# Analog_Inputs.net
KiCad netlist of a schematic drawn in Altium Designer
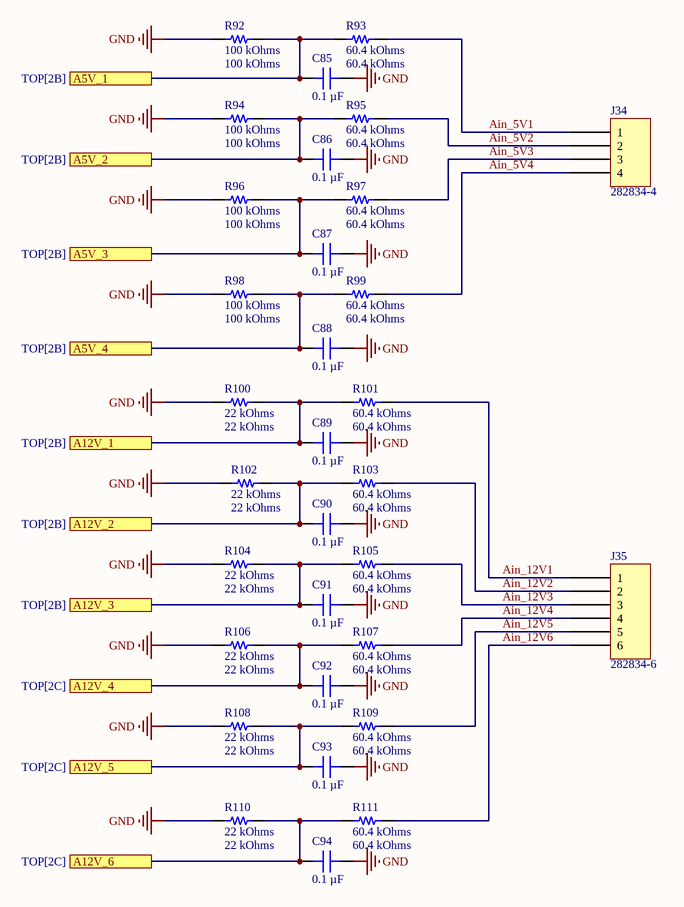
[diagram p0: Analog Inputs.SchDoc]

(export (version "E")
  (design (tool "Eeschema 10.0.6"))
  (components
    (comp (ref "C85")
      (value "0.1 µF")
      (footprint "CAP 0603_1608")
      (description "CAP CER 0.1UF 6.3V X7R 0603")
      (fields
        (field (name "PART NUMBER") "6R3X14W104MV4T")
        (field (name "MANUFACTURER") "Johanson Dielectrics Inc.")
      )
      (libsource (lib "altium_library") (part "Capacitor"))
    )
    (comp (ref "C86")
      (value "0.1 µF")
      (footprint "CAP 0603_1608")
      (description "CAP CER 0.1UF 6.3V X7R 0603")
      (fields
        (field (name "PART NUMBER") "6R3X14W104MV4T")
        (field (name "MANUFACTURER") "Johanson Dielectrics Inc.")
      )
      (libsource (lib "altium_library") (part "Capacitor"))
    )
    (comp (ref "C87")
      (value "0.1 µF")
      (footprint "CAP 0603_1608")
      (description "CAP CER 0.1UF 6.3V X7R 0603")
      (fields
        (field (name "PART NUMBER") "6R3X14W104MV4T")
        (field (name "MANUFACTURER") "Johanson Dielectrics Inc.")
      )
      (libsource (lib "altium_library") (part "Capacitor"))
    )
    (comp (ref "C88")
      (value "0.1 µF")
      (footprint "CAP 0603_1608")
      (description "CAP CER 0.1UF 6.3V X7R 0603")
      (fields
        (field (name "PART NUMBER") "6R3X14W104MV4T")
        (field (name "MANUFACTURER") "Johanson Dielectrics Inc.")
      )
      (libsource (lib "altium_library") (part "Capacitor"))
    )
    (comp (ref "C89")
      (value "0.1 µF")
      (footprint "CAP 0603_1608")
      (description "CAP CER 0.1UF 6.3V X7R 0603")
      (fields
        (field (name "PART NUMBER") "6R3X14W104MV4T")
        (field (name "MANUFACTURER") "Johanson Dielectrics Inc.")
      )
      (libsource (lib "altium_library") (part "Capacitor"))
    )
    (comp (ref "C90")
      (value "0.1 µF")
      (footprint "CAP 0603_1608")
      (description "CAP CER 0.1UF 6.3V X7R 0603")
      (fields
        (field (name "PART NUMBER") "6R3X14W104MV4T")
        (field (name "MANUFACTURER") "Johanson Dielectrics Inc.")
      )
      (libsource (lib "altium_library") (part "Capacitor"))
    )
    (comp (ref "C91")
      (value "0.1 µF")
      (footprint "CAP 0603_1608")
      (description "CAP CER 0.1UF 6.3V X7R 0603")
      (fields
        (field (name "PART NUMBER") "6R3X14W104MV4T")
        (field (name "MANUFACTURER") "Johanson Dielectrics Inc.")
      )
      (libsource (lib "altium_library") (part "Capacitor"))
    )
    (comp (ref "C92")
      (value "0.1 µF")
      (footprint "CAP 0603_1608")
      (description "CAP CER 0.1UF 6.3V X7R 0603")
      (fields
        (field (name "PART NUMBER") "6R3X14W104MV4T")
        (field (name "MANUFACTURER") "Johanson Dielectrics Inc.")
      )
      (libsource (lib "altium_library") (part "Capacitor"))
    )
    (comp (ref "C93")
      (value "0.1 µF")
      (footprint "CAP 0603_1608")
      (description "CAP CER 0.1UF 6.3V X7R 0603")
      (fields
        (field (name "PART NUMBER") "6R3X14W104MV4T")
        (field (name "MANUFACTURER") "Johanson Dielectrics Inc.")
      )
      (libsource (lib "altium_library") (part "Capacitor"))
    )
    (comp (ref "C94")
      (value "0.1 µF")
      (footprint "CAP 0603_1608")
      (description "CAP CER 0.1UF 6.3V X7R 0603")
      (fields
        (field (name "PART NUMBER") "6R3X14W104MV4T")
        (field (name "MANUFACTURER") "Johanson Dielectrics Inc.")
      )
      (libsource (lib "altium_library") (part "Capacitor"))
    )
    (comp (ref "J34")
      (value "282834-4")
      (footprint "TE 282834-4")
      (description "TERM BLK 4P SIDE ENT 2.54MM PCB")
      (fields (field (name "MANUFACTURER") "TE Connectivity AMP Connectors") (field (name "VOLTAGE") "150V"))
      (libsource (lib "altium_library") (part "4 Pin"))
    )
    (comp (ref "J35")
      (value "282834-6")
      (footprint "TE 282834-6")
      (description "TERM BLK 6P SIDE ENT 2.54MM PCB")
      (fields (field (name "MANUFACTURER") "TE Connectivity AMP Connectors") (field (name "VOLTAGE") "150V"))
      (libsource (lib "altium_library") (part "6 Pin"))
    )
    (comp (ref "R92")
      (value "100 kOhms")
      (footprint "RES 0603_1608")
      (description "RES SMD 100K OHM 1% 1/10W 0603")
      (fields (field (name "PART NUMBER") "AA0603FR-07100KL") (field (name "ALTIUM_VALUE") "100 kOhms"))
      (libsource (lib "altium_library") (part "Resistor"))
    )
    (comp (ref "R93")
      (value "60.4 kOhms")
      (footprint "RES 0603_1608")
      (description "RES SMD 60.4K OHM 1% 1/10W 0603")
      (fields (field (name "PART NUMBER") "AC0603FR-0760K4L") (field (name "ALTIUM_VALUE") "60.4 kOhms"))
      (libsource (lib "altium_library") (part "Resistor"))
    )
    (comp (ref "R94")
      (value "100 kOhms")
      (footprint "RES 0603_1608")
      (description "RES SMD 100K OHM 1% 1/10W 0603")
      (fields (field (name "PART NUMBER") "AA0603FR-07100KL") (field (name "ALTIUM_VALUE") "100 kOhms"))
      (libsource (lib "altium_library") (part "Resistor"))
    )
    (comp (ref "R95")
      (value "60.4 kOhms")
      (footprint "RES 0603_1608")
      (description "RES SMD 60.4K OHM 1% 1/10W 0603")
      (fields (field (name "PART NUMBER") "AC0603FR-0760K4L") (field (name "ALTIUM_VALUE") "60.4 kOhms"))
      (libsource (lib "altium_library") (part "Resistor"))
    )
    (comp (ref "R96")
      (value "100 kOhms")
      (footprint "RES 0603_1608")
      (description "RES SMD 100K OHM 1% 1/10W 0603")
      (fields (field (name "PART NUMBER") "AA0603FR-07100KL") (field (name "ALTIUM_VALUE") "100 kOhms"))
      (libsource (lib "altium_library") (part "Resistor"))
    )
    (comp (ref "R97")
      (value "60.4 kOhms")
      (footprint "RES 0603_1608")
      (description "RES SMD 60.4K OHM 1% 1/10W 0603")
      (fields (field (name "PART NUMBER") "AC0603FR-0760K4L") (field (name "ALTIUM_VALUE") "60.4 kOhms"))
      (libsource (lib "altium_library") (part "Resistor"))
    )
    (comp (ref "R98")
      (value "100 kOhms")
      (footprint "RES 0603_1608")
      (description "RES SMD 100K OHM 1% 1/10W 0603")
      (fields (field (name "PART NUMBER") "AA0603FR-07100KL") (field (name "ALTIUM_VALUE") "100 kOhms"))
      (libsource (lib "altium_library") (part "Resistor"))
    )
    (comp (ref "R99")
      (value "60.4 kOhms")
      (footprint "RES 0603_1608")
      (description "RES SMD 60.4K OHM 1% 1/10W 0603")
      (fields (field (name "PART NUMBER") "AC0603FR-0760K4L") (field (name "ALTIUM_VALUE") "60.4 kOhms"))
      (libsource (lib "altium_library") (part "Resistor"))
    )
    (comp (ref "R100")
      (value "22 kOhms")
      (footprint "RES 0603_1608")
      (description "RES 22K OHM 1% 1/5W 0603")
      (fields (field (name "PART NUMBER") "AC0603FR-7W22KL") (field (name "ALTIUM_VALUE") "22 kOhms"))
      (libsource (lib "altium_library") (part "Resistor"))
    )
    (comp (ref "R101")
      (value "60.4 kOhms")
      (footprint "RES 0603_1608")
      (description "RES SMD 60.4K OHM 1% 1/10W 0603")
      (fields (field (name "PART NUMBER") "AC0603FR-0760K4L") (field (name "ALTIUM_VALUE") "60.4 kOhms"))
      (libsource (lib "altium_library") (part "Resistor"))
    )
    (comp (ref "R102")
      (value "22 kOhms")
      (footprint "RES 0603_1608")
      (description "RES 22K OHM 1% 1/5W 0603")
      (fields (field (name "PART NUMBER") "AC0603FR-7W22KL") (field (name "ALTIUM_VALUE") "22 kOhms"))
      (libsource (lib "altium_library") (part "Resistor"))
    )
    (comp (ref "R103")
      (value "60.4 kOhms")
      (footprint "RES 0603_1608")
      (description "RES SMD 60.4K OHM 1% 1/10W 0603")
      (fields (field (name "PART NUMBER") "AC0603FR-0760K4L") (field (name "ALTIUM_VALUE") "60.4 kOhms"))
      (libsource (lib "altium_library") (part "Resistor"))
    )
    (comp (ref "R104")
      (value "22 kOhms")
      (footprint "RES 0603_1608")
      (description "RES 22K OHM 1% 1/5W 0603")
      (fields (field (name "PART NUMBER") "AC0603FR-7W22KL") (field (name "ALTIUM_VALUE") "22 kOhms"))
      (libsource (lib "altium_library") (part "Resistor"))
    )
    (comp (ref "R105")
      (value "60.4 kOhms")
      (footprint "RES 0603_1608")
      (description "RES SMD 60.4K OHM 1% 1/10W 0603")
      (fields (field (name "PART NUMBER") "AC0603FR-0760K4L") (field (name "ALTIUM_VALUE") "60.4 kOhms"))
      (libsource (lib "altium_library") (part "Resistor"))
    )
    (comp (ref "R106")
      (value "22 kOhms")
      (footprint "RES 0603_1608")
      (description "RES 22K OHM 1% 1/5W 0603")
      (fields (field (name "PART NUMBER") "AC0603FR-7W22KL") (field (name "ALTIUM_VALUE") "22 kOhms"))
      (libsource (lib "altium_library") (part "Resistor"))
    )
    (comp (ref "R107")
      (value "60.4 kOhms")
      (footprint "RES 0603_1608")
      (description "RES SMD 60.4K OHM 1% 1/10W 0603")
      (fields (field (name "PART NUMBER") "AC0603FR-0760K4L") (field (name "ALTIUM_VALUE") "60.4 kOhms"))
      (libsource (lib "altium_library") (part "Resistor"))
    )
    (comp (ref "R108")
      (value "22 kOhms")
      (footprint "RES 0603_1608")
      (description "RES 22K OHM 1% 1/5W 0603")
      (fields (field (name "PART NUMBER") "AC0603FR-7W22KL") (field (name "ALTIUM_VALUE") "22 kOhms"))
      (libsource (lib "altium_library") (part "Resistor"))
    )
    (comp (ref "R109")
      (value "60.4 kOhms")
      (footprint "RES 0603_1608")
      (description "RES SMD 60.4K OHM 1% 1/10W 0603")
      (fields (field (name "PART NUMBER") "AC0603FR-0760K4L") (field (name "ALTIUM_VALUE") "60.4 kOhms"))
      (libsource (lib "altium_library") (part "Resistor"))
    )
    (comp (ref "R110")
      (value "22 kOhms")
      (footprint "RES 0603_1608")
      (description "RES 22K OHM 1% 1/5W 0603")
      (fields (field (name "PART NUMBER") "AC0603FR-7W22KL") (field (name "ALTIUM_VALUE") "22 kOhms"))
      (libsource (lib "altium_library") (part "Resistor"))
    )
    (comp (ref "R111")
      (value "60.4 kOhms")
      (footprint "RES 0603_1608")
      (description "RES SMD 60.4K OHM 1% 1/10W 0603")
      (fields (field (name "PART NUMBER") "AC0603FR-0760K4L") (field (name "ALTIUM_VALUE") "60.4 kOhms"))
      (libsource (lib "altium_library") (part "Resistor"))
    )
  )
  (nets
    (net (code "1") (name "/A5V_1") (class "Default")
      (node (ref "C85") (pin "1") (pinfunction "1_1") (pintype "passive"))
      (node (ref "R92") (pin "2") (pinfunction "2_2") (pintype "passive"))
      (node (ref "R93") (pin "1") (pinfunction "1_1") (pintype "passive"))
    )
    (net (code "2") (name "/A5V_2") (class "Default")
      (node (ref "C86") (pin "1") (pinfunction "1_1") (pintype "passive"))
      (node (ref "R94") (pin "2") (pinfunction "2_2") (pintype "passive"))
      (node (ref "R95") (pin "1") (pinfunction "1_1") (pintype "passive"))
    )
    (net (code "3") (name "/A5V_3") (class "Default")
      (node (ref "C87") (pin "1") (pinfunction "1_1") (pintype "passive"))
      (node (ref "R96") (pin "2") (pinfunction "2_2") (pintype "passive"))
      (node (ref "R97") (pin "1") (pinfunction "1_1") (pintype "passive"))
    )
    (net (code "4") (name "/A5V_4") (class "Default")
      (node (ref "C88") (pin "1") (pinfunction "1_1") (pintype "passive"))
      (node (ref "R98") (pin "2") (pinfunction "2_2") (pintype "passive"))
      (node (ref "R99") (pin "1") (pinfunction "1_1") (pintype "passive"))
    )
    (net (code "5") (name "/A12V_1") (class "Default")
      (node (ref "C89") (pin "1") (pinfunction "1_1") (pintype "passive"))
      (node (ref "R100") (pin "1") (pinfunction "1_1") (pintype "passive"))
      (node (ref "R101") (pin "2") (pinfunction "2_2") (pintype "passive"))
    )
    (net (code "6") (name "/A12V_2") (class "Default")
      (node (ref "C90") (pin "1") (pinfunction "1_1") (pintype "passive"))
      (node (ref "R102") (pin "1") (pinfunction "1_1") (pintype "passive"))
      (node (ref "R103") (pin "2") (pinfunction "2_2") (pintype "passive"))
    )
    (net (code "7") (name "/A12V_3") (class "Default")
      (node (ref "C91") (pin "1") (pinfunction "1_1") (pintype "passive"))
      (node (ref "R104") (pin "1") (pinfunction "1_1") (pintype "passive"))
      (node (ref "R105") (pin "2") (pinfunction "2_2") (pintype "passive"))
    )
    (net (code "8") (name "/A12V_4") (class "Default")
      (node (ref "C92") (pin "1") (pinfunction "1_1") (pintype "passive"))
      (node (ref "R106") (pin "1") (pinfunction "1_1") (pintype "passive"))
      (node (ref "R107") (pin "2") (pinfunction "2_2") (pintype "passive"))
    )
    (net (code "9") (name "/A12V_5") (class "Default")
      (node (ref "C93") (pin "1") (pinfunction "1_1") (pintype "passive"))
      (node (ref "R108") (pin "1") (pinfunction "1_1") (pintype "passive"))
      (node (ref "R109") (pin "2") (pinfunction "2_2") (pintype "passive"))
    )
    (net (code "10") (name "/A12V_6") (class "Default")
      (node (ref "C94") (pin "1") (pinfunction "1_1") (pintype "passive"))
      (node (ref "R110") (pin "1") (pinfunction "1_1") (pintype "passive"))
      (node (ref "R111") (pin "2") (pinfunction "2_2") (pintype "passive"))
    )
    (net (code "11") (name "/Ain_5V1") (class "Default")
      (node (ref "J34") (pin "1") (pinfunction "1_1") (pintype "passive"))
      (node (ref "R93") (pin "2") (pinfunction "2_2") (pintype "passive"))
    )
    (net (code "12") (name "/Ain_5V2") (class "Default")
      (node (ref "J34") (pin "2") (pinfunction "2_2") (pintype "passive"))
      (node (ref "R95") (pin "2") (pinfunction "2_2") (pintype "passive"))
    )
    (net (code "13") (name "/Ain_5V3") (class "Default")
      (node (ref "J34") (pin "3") (pinfunction "3_3") (pintype "passive"))
      (node (ref "R97") (pin "2") (pinfunction "2_2") (pintype "passive"))
    )
    (net (code "14") (name "/Ain_5V4") (class "Default")
      (node (ref "J34") (pin "4") (pinfunction "4_4") (pintype "passive"))
      (node (ref "R99") (pin "2") (pinfunction "2_2") (pintype "passive"))
    )
    (net (code "15") (name "/Ain_12V1") (class "Default")
      (node (ref "J35") (pin "1") (pinfunction "1_1") (pintype "passive"))
      (node (ref "R101") (pin "1") (pinfunction "1_1") (pintype "passive"))
    )
    (net (code "16") (name "/Ain_12V2") (class "Default")
      (node (ref "J35") (pin "2") (pinfunction "2_2") (pintype "passive"))
      (node (ref "R103") (pin "1") (pinfunction "1_1") (pintype "passive"))
    )
    (net (code "17") (name "/Ain_12V3") (class "Default")
      (node (ref "J35") (pin "3") (pinfunction "3_3") (pintype "passive"))
      (node (ref "R105") (pin "1") (pinfunction "1_1") (pintype "passive"))
    )
    (net (code "18") (name "/Ain_12V4") (class "Default")
      (node (ref "J35") (pin "4") (pinfunction "4_4") (pintype "passive"))
      (node (ref "R107") (pin "1") (pinfunction "1_1") (pintype "passive"))
    )
    (net (code "19") (name "/Ain_12V5") (class "Default")
      (node (ref "J35") (pin "5") (pinfunction "5_5") (pintype "passive"))
      (node (ref "R109") (pin "1") (pinfunction "1_1") (pintype "passive"))
    )
    (net (code "20") (name "/Ain_12V6") (class "Default")
      (node (ref "J35") (pin "6") (pinfunction "6_6") (pintype "passive"))
      (node (ref "R111") (pin "1") (pinfunction "1_1") (pintype "passive"))
    )
    (net (code "21") (name "GND") (class "Default")
      (node (ref "C85") (pin "2") (pinfunction "2_2") (pintype "passive"))
      (node (ref "C86") (pin "2") (pinfunction "2_2") (pintype "passive"))
      (node (ref "C87") (pin "2") (pinfunction "2_2") (pintype "passive"))
      (node (ref "C88") (pin "2") (pinfunction "2_2") (pintype "passive"))
      (node (ref "C89") (pin "2") (pinfunction "2_2") (pintype "passive"))
      (node (ref "C90") (pin "2") (pinfunction "2_2") (pintype "passive"))
      (node (ref "C91") (pin "2") (pinfunction "2_2") (pintype "passive"))
      (node (ref "C92") (pin "2") (pinfunction "2_2") (pintype "passive"))
      (node (ref "C93") (pin "2") (pinfunction "2_2") (pintype "passive"))
      (node (ref "C94") (pin "2") (pinfunction "2_2") (pintype "passive"))
      (node (ref "R100") (pin "2") (pinfunction "2_2") (pintype "passive"))
      (node (ref "R102") (pin "2") (pinfunction "2_2") (pintype "passive"))
      (node (ref "R104") (pin "2") (pinfunction "2_2") (pintype "passive"))
      (node (ref "R106") (pin "2") (pinfunction "2_2") (pintype "passive"))
      (node (ref "R108") (pin "2") (pinfunction "2_2") (pintype "passive"))
      (node (ref "R110") (pin "2") (pinfunction "2_2") (pintype "passive"))
      (node (ref "R92") (pin "1") (pinfunction "1_1") (pintype "passive"))
      (node (ref "R94") (pin "1") (pinfunction "1_1") (pintype "passive"))
      (node (ref "R96") (pin "1") (pinfunction "1_1") (pintype "passive"))
      (node (ref "R98") (pin "1") (pinfunction "1_1") (pintype "passive"))
    )
  )
)
